# TSOC_WaterSensor.net
KiCad netlist of a schematic drawn in EAGLE
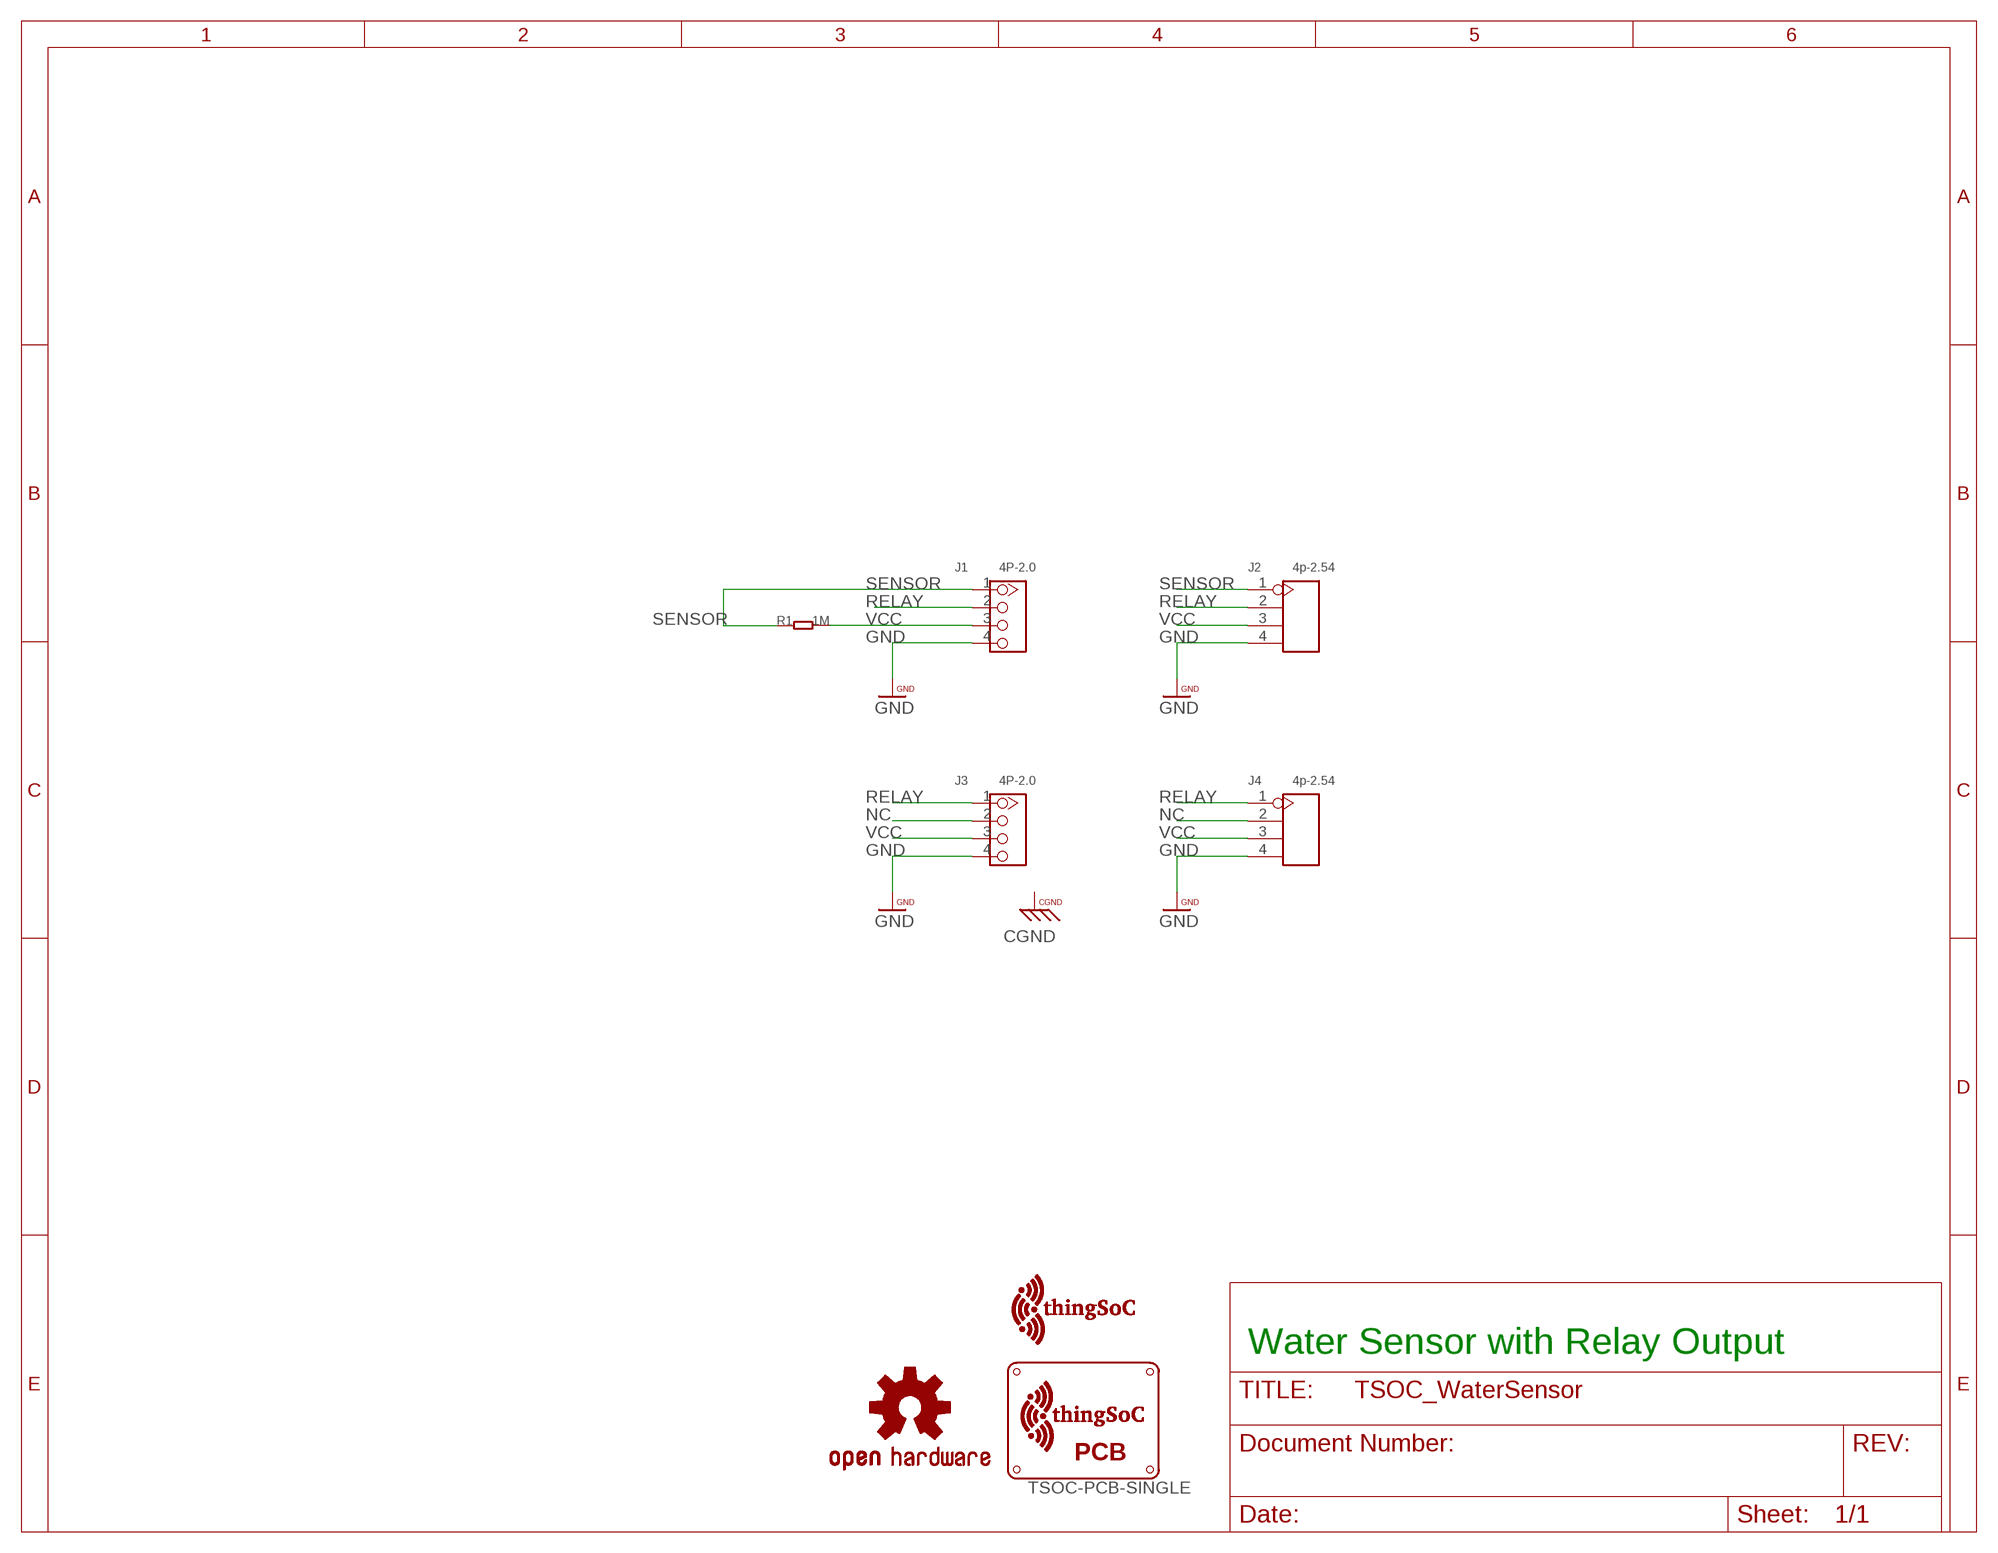
[diagram p0: schematic, sheet 1]

(export (version "E")
  (design (tool "Eeschema 10.0.6"))
  (components
    (comp (ref "J1")
      (value "4P-2.0")
      (footprint "eagle-import:HW4-2.0")
      (libsource (lib "eagle-import") (part "GROVE-CONNECTOR-DIP(4P-2.0)"))
    )
    (comp (ref "J2")
      (value "4p-2.54")
      (footprint "eagle-import:H4-2.54")
      (fields (field (name "MPN") "P125-1104A0BS116A1"))
      (libsource (lib "eagle-import") (part "DIP-BLACK-MALE-HEADER-VERT(4P-2.54)"))
    )
    (comp (ref "J3")
      (value "4P-2.0")
      (footprint "eagle-import:HW4-2.0")
      (libsource (lib "eagle-import") (part "GROVE-CONNECTOR-DIP(4P-2.0)"))
    )
    (comp (ref "J4")
      (value "4p-2.54")
      (footprint "eagle-import:H4-2.54")
      (fields (field (name "MPN") "P125-1104A0BS116A1"))
      (libsource (lib "eagle-import") (part "DIP-BLACK-MALE-HEADER-VERT(4P-2.54)"))
    )
    (comp (ref "R1")
      (value "1M")
      (footprint "eagle-import:0603")
      (libsource (lib "eagle-import") (part "R0603"))
    )
    (comp (ref "U$1")
      (value "OSHW_LOGO_SYMM")
      (footprint "eagle-import:OSHW_LOGO_MED_SYM")
      (libsource (lib "eagle-import") (part "OSHW_LOGO_SYMM"))
    )
    (comp (ref "U$2")
      (value "TSOC-LOGO-LRG")
      (footprint "eagle-import:TSOC-LOGO-LRG")
      (libsource (lib "eagle-import") (part "TSOC-LOGO-LRG"))
    )
    (comp (ref "U$3")
      (value "TSOC-PCB-SINGLE")
      (footprint "eagle-import:TSOC-BB-BRD-DIM")
      (libsource (lib "eagle-import") (part "TSOC-PCB-SINGLE"))
    )
  )
  (nets
    (net (code "1") (name "/NC") (class "Default")
      (node (ref "J3") (pin "2") (pinfunction "2_2") (pintype "bidirectional"))
      (node (ref "J4") (pin "2") (pinfunction "P$2_2") (pintype "bidirectional"))
    )
    (net (code "2") (name "/RELAY") (class "Default")
      (node (ref "J1") (pin "2") (pinfunction "2_2") (pintype "bidirectional"))
      (node (ref "J2") (pin "2") (pinfunction "P$2_2") (pintype "bidirectional"))
      (node (ref "J3") (pin "1") (pinfunction "1_1") (pintype "bidirectional"))
      (node (ref "J4") (pin "1") (pinfunction "P$1_1") (pintype "bidirectional"))
    )
    (net (code "3") (name "/SENSOR") (class "Default")
      (node (ref "J1") (pin "1") (pinfunction "1_1") (pintype "bidirectional"))
      (node (ref "J2") (pin "1") (pinfunction "P$1_1") (pintype "bidirectional"))
      (node (ref "R1") (pin "1") (pinfunction "1_1") (pintype "bidirectional"))
    )
    (net (code "4") (name "/VCC") (class "Default")
      (node (ref "J1") (pin "3") (pinfunction "3_3") (pintype "bidirectional"))
      (node (ref "J2") (pin "3") (pinfunction "P$3_3") (pintype "bidirectional"))
      (node (ref "J3") (pin "3") (pinfunction "3_3") (pintype "bidirectional"))
      (node (ref "J4") (pin "3") (pinfunction "P$3_3") (pintype "bidirectional"))
      (node (ref "R1") (pin "2") (pinfunction "2_2") (pintype "bidirectional"))
    )
    (net (code "6") (name "GND") (class "Default")
      (node (ref "J1") (pin "4") (pinfunction "4_4") (pintype "bidirectional"))
      (node (ref "J2") (pin "4") (pinfunction "P$4_4") (pintype "bidirectional"))
      (node (ref "J3") (pin "4") (pinfunction "4_4") (pintype "bidirectional"))
      (node (ref "J4") (pin "4") (pinfunction "P$4_4") (pintype "bidirectional"))
    )
  )
)
